# headstage-with-omnetics.net
KiCad netlist of a schematic drawn in EAGLE
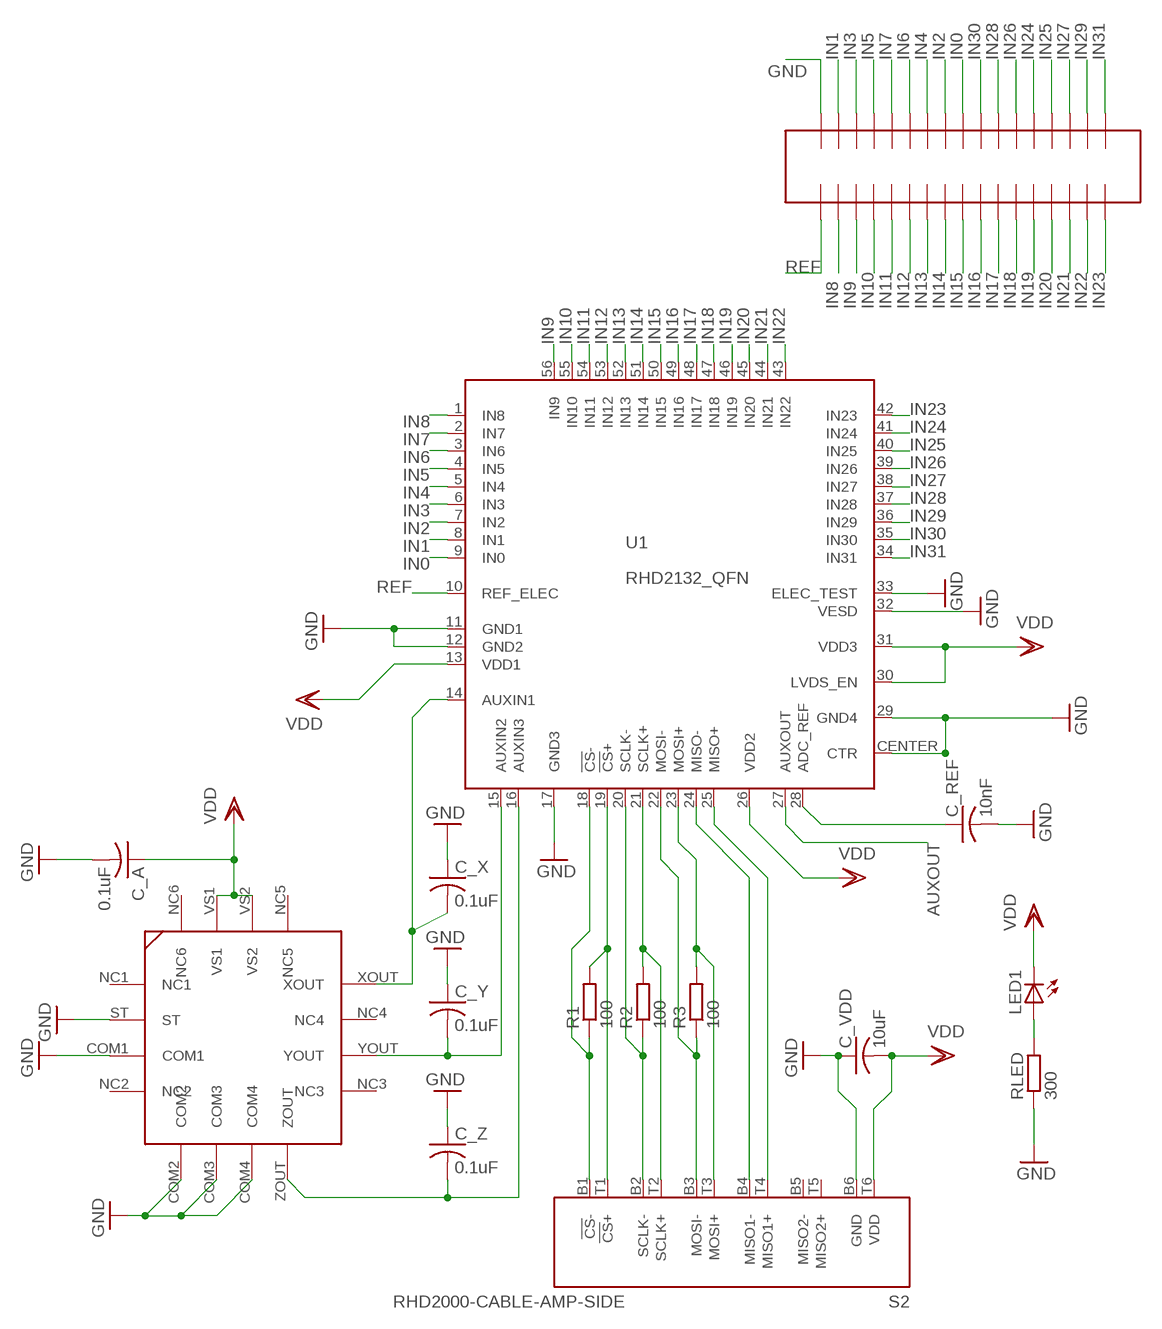
[diagram p0: schematic, sheet 1]

(export (version "E")
  (design (tool "Eeschema 10.0.6"))
  (components
    (comp (ref "C_A")
      (value "0.1uF")
      (footprint "eagle-import:C0402K")
      (libsource (lib "eagle-import") (part "resistor_C-USC0402K"))
    )
    (comp (ref "C_REF")
      (value "10nF")
      (footprint "eagle-import:C0402K")
      (libsource (lib "eagle-import") (part "resistor_C-USC0402K"))
    )
    (comp (ref "C_VDD")
      (value "10uF")
      (footprint "eagle-import:C0805")
      (libsource (lib "eagle-import") (part "C-USC0805"))
    )
    (comp (ref "C_X")
      (value "0.1uF")
      (footprint "eagle-import:C0402K")
      (libsource (lib "eagle-import") (part "resistor_C-USC0402K"))
    )
    (comp (ref "C_Y")
      (value "0.1uF")
      (footprint "eagle-import:C0402K")
      (libsource (lib "eagle-import") (part "resistor_C-USC0402K"))
    )
    (comp (ref "C_Z")
      (value "0.1uF")
      (footprint "eagle-import:C0402K")
      (libsource (lib "eagle-import") (part "resistor_C-USC0402K"))
    )
    (comp (ref "LED1")
      (value "LEDCHIPLED_0805")
      (footprint "eagle-import:CHIPLED_0805")
      (libsource (lib "eagle-import") (part "LEDCHIPLED_0805"))
    )
    (comp (ref "R1")
      (value "100")
      (footprint "eagle-import:R0402")
      (libsource (lib "eagle-import") (part "R-EU_R0402"))
    )
    (comp (ref "R2")
      (value "100")
      (footprint "eagle-import:R0402")
      (libsource (lib "eagle-import") (part "R-EU_R0402"))
    )
    (comp (ref "R3")
      (value "100")
      (footprint "eagle-import:R0402")
      (libsource (lib "eagle-import") (part "R-EU_R0402"))
    )
    (comp (ref "RLED")
      (value "300")
      (footprint "eagle-import:R0402")
      (libsource (lib "eagle-import") (part "R-EU_R0402"))
    )
    (comp (ref "S2")
      (value "RHD2000-CABLE-AMP-SIDE")
      (footprint "eagle-import:OMNETICS_PZN-12-AA")
      (libsource (lib "eagle-import") (part "RHD2000-CABLE-AMP-SIDE"))
    )
    (comp (ref "U$1")
      (value "ADXL335")
      (footprint "eagle-import:ADXL335")
      (libsource (lib "eagle-import") (part "ADXL335"))
    )
    (comp (ref "U$2")
      (value "FTSH-117BOARD-END")
      (footprint "eagle-import:FTSH-117-END")
      (libsource (lib "eagle-import") (part "FTSH-117BOARD-END"))
    )
    (comp (ref "U1")
      (value "RHD2132_QFN")
      (footprint "eagle-import:QFN56_8_X_8_LARGE")
      (libsource (lib "eagle-import") (part "RHD2132_QFN"))
    )
  )
  (nets
    (net (code "1") (name "/AUXOUT") (class "Default")
      (node (ref "U1") (pin "27") (pinfunction "AUXOUT_27") (pintype "tri_state"))
    )
    (net (code "2") (name "/IN0") (class "Default")
      (node (ref "U$2") (pin "P$26") (pinfunction "P$26_P$26") (pintype "bidirectional"))
      (node (ref "U1") (pin "9") (pinfunction "IN0_9") (pintype "input"))
    )
    (net (code "3") (name "/IN1") (class "Default")
      (node (ref "U$2") (pin "P$33") (pinfunction "P$33_P$33") (pintype "bidirectional"))
      (node (ref "U1") (pin "8") (pinfunction "IN1_8") (pintype "input"))
    )
    (net (code "4") (name "/IN2") (class "Default")
      (node (ref "U$2") (pin "P$27") (pinfunction "P$27_P$27") (pintype "bidirectional"))
      (node (ref "U1") (pin "7") (pinfunction "IN2_7") (pintype "input"))
    )
    (net (code "5") (name "/IN3") (class "Default")
      (node (ref "U$2") (pin "P$32") (pinfunction "P$32_P$32") (pintype "bidirectional"))
      (node (ref "U1") (pin "6") (pinfunction "IN3_6") (pintype "input"))
    )
    (net (code "6") (name "/IN4") (class "Default")
      (node (ref "U$2") (pin "P$28") (pinfunction "P$28_P$28") (pintype "bidirectional"))
      (node (ref "U1") (pin "5") (pinfunction "IN4_5") (pintype "input"))
    )
    (net (code "7") (name "/IN5") (class "Default")
      (node (ref "U$2") (pin "P$31") (pinfunction "P$31_P$31") (pintype "bidirectional"))
      (node (ref "U1") (pin "4") (pinfunction "IN5_4") (pintype "input"))
    )
    (net (code "8") (name "/IN6") (class "Default")
      (node (ref "U$2") (pin "P$29") (pinfunction "P$29_P$29") (pintype "bidirectional"))
      (node (ref "U1") (pin "3") (pinfunction "IN6_3") (pintype "input"))
    )
    (net (code "9") (name "/IN7") (class "Default")
      (node (ref "U$2") (pin "P$30") (pinfunction "P$30_P$30") (pintype "bidirectional"))
      (node (ref "U1") (pin "2") (pinfunction "IN7_2") (pintype "input"))
    )
    (net (code "10") (name "/IN8") (class "Default")
      (node (ref "U$2") (pin "P$2") (pinfunction "P$2_P$2") (pintype "bidirectional"))
      (node (ref "U1") (pin "1") (pinfunction "IN8_1") (pintype "input"))
    )
    (net (code "11") (name "/IN9") (class "Default")
      (node (ref "U$2") (pin "P$3") (pinfunction "P$3_P$3") (pintype "bidirectional"))
      (node (ref "U1") (pin "56") (pinfunction "IN9_56") (pintype "input"))
    )
    (net (code "12") (name "/IN10") (class "Default")
      (node (ref "U$2") (pin "P$4") (pinfunction "P$4_P$4") (pintype "bidirectional"))
      (node (ref "U1") (pin "55") (pinfunction "IN10_55") (pintype "input"))
    )
    (net (code "13") (name "/IN11") (class "Default")
      (node (ref "U$2") (pin "P$5") (pinfunction "P$5_P$5") (pintype "bidirectional"))
      (node (ref "U1") (pin "54") (pinfunction "IN11_54") (pintype "input"))
    )
    (net (code "14") (name "/IN12") (class "Default")
      (node (ref "U$2") (pin "P$6") (pinfunction "P$6_P$6") (pintype "bidirectional"))
      (node (ref "U1") (pin "53") (pinfunction "IN12_53") (pintype "input"))
    )
    (net (code "15") (name "/IN13") (class "Default")
      (node (ref "U$2") (pin "P$7") (pinfunction "P$7_P$7") (pintype "bidirectional"))
      (node (ref "U1") (pin "52") (pinfunction "IN13_52") (pintype "input"))
    )
    (net (code "16") (name "/IN14") (class "Default")
      (node (ref "U$2") (pin "P$8") (pinfunction "P$8_P$8") (pintype "bidirectional"))
      (node (ref "U1") (pin "51") (pinfunction "IN14_51") (pintype "input"))
    )
    (net (code "17") (name "/IN15") (class "Default")
      (node (ref "U$2") (pin "P$9") (pinfunction "P$9_P$9") (pintype "bidirectional"))
      (node (ref "U1") (pin "50") (pinfunction "IN15_50") (pintype "input"))
    )
    (net (code "18") (name "/IN16") (class "Default")
      (node (ref "U$2") (pin "P$10") (pinfunction "P$10_P$10") (pintype "bidirectional"))
      (node (ref "U1") (pin "49") (pinfunction "IN16_49") (pintype "input"))
    )
    (net (code "19") (name "/IN17") (class "Default")
      (node (ref "U$2") (pin "P$11") (pinfunction "P$11_P$11") (pintype "bidirectional"))
      (node (ref "U1") (pin "48") (pinfunction "IN17_48") (pintype "input"))
    )
    (net (code "20") (name "/IN18") (class "Default")
      (node (ref "U$2") (pin "P$12") (pinfunction "P$12_P$12") (pintype "bidirectional"))
      (node (ref "U1") (pin "47") (pinfunction "IN18_47") (pintype "input"))
    )
    (net (code "21") (name "/IN19") (class "Default")
      (node (ref "U$2") (pin "P$13") (pinfunction "P$13_P$13") (pintype "bidirectional"))
      (node (ref "U1") (pin "46") (pinfunction "IN19_46") (pintype "input"))
    )
    (net (code "22") (name "/IN20") (class "Default")
      (node (ref "U$2") (pin "P$14") (pinfunction "P$14_P$14") (pintype "bidirectional"))
      (node (ref "U1") (pin "45") (pinfunction "IN20_45") (pintype "input"))
    )
    (net (code "23") (name "/IN21") (class "Default")
      (node (ref "U$2") (pin "P$15") (pinfunction "P$15_P$15") (pintype "bidirectional"))
      (node (ref "U1") (pin "44") (pinfunction "IN21_44") (pintype "input"))
    )
    (net (code "24") (name "/IN22") (class "Default")
      (node (ref "U$2") (pin "P$16") (pinfunction "P$16_P$16") (pintype "bidirectional"))
      (node (ref "U1") (pin "43") (pinfunction "IN22_43") (pintype "input"))
    )
    (net (code "25") (name "/IN23") (class "Default")
      (node (ref "U$2") (pin "P$17") (pinfunction "P$17_P$17") (pintype "bidirectional"))
      (node (ref "U1") (pin "42") (pinfunction "IN23_42") (pintype "input"))
    )
    (net (code "26") (name "/IN24") (class "Default")
      (node (ref "U$2") (pin "P$22") (pinfunction "P$22_P$22") (pintype "bidirectional"))
      (node (ref "U1") (pin "41") (pinfunction "IN24_41") (pintype "input"))
    )
    (net (code "27") (name "/IN25") (class "Default")
      (node (ref "U$2") (pin "P$21") (pinfunction "P$21_P$21") (pintype "bidirectional"))
      (node (ref "U1") (pin "40") (pinfunction "IN25_40") (pintype "input"))
    )
    (net (code "28") (name "/IN26") (class "Default")
      (node (ref "U$2") (pin "P$23") (pinfunction "P$23_P$23") (pintype "bidirectional"))
      (node (ref "U1") (pin "39") (pinfunction "IN26_39") (pintype "input"))
    )
    (net (code "29") (name "/IN27") (class "Default")
      (node (ref "U$2") (pin "P$20") (pinfunction "P$20_P$20") (pintype "bidirectional"))
      (node (ref "U1") (pin "38") (pinfunction "IN27_38") (pintype "input"))
    )
    (net (code "30") (name "/IN28") (class "Default")
      (node (ref "U$2") (pin "P$24") (pinfunction "P$24_P$24") (pintype "bidirectional"))
      (node (ref "U1") (pin "37") (pinfunction "IN28_37") (pintype "input"))
    )
    (net (code "31") (name "/IN29") (class "Default")
      (node (ref "U$2") (pin "P$19") (pinfunction "P$19_P$19") (pintype "bidirectional"))
      (node (ref "U1") (pin "36") (pinfunction "IN29_36") (pintype "input"))
    )
    (net (code "32") (name "/IN30") (class "Default")
      (node (ref "U$2") (pin "P$25") (pinfunction "P$25_P$25") (pintype "bidirectional"))
      (node (ref "U1") (pin "35") (pinfunction "IN30_35") (pintype "input"))
    )
    (net (code "33") (name "/IN31") (class "Default")
      (node (ref "U$2") (pin "P$18") (pinfunction "P$18_P$18") (pintype "bidirectional"))
      (node (ref "U1") (pin "34") (pinfunction "IN31_34") (pintype "input"))
    )
    (net (code "34") (name "/REF") (class "Default")
      (node (ref "U$2") (pin "P$1") (pinfunction "P$1_P$1") (pintype "bidirectional"))
      (node (ref "U1") (pin "10") (pinfunction "REF_ELEC_10") (pintype "input"))
    )
    (net (code "35") (name "GND") (class "Default")
      (node (ref "C_A") (pin "2") (pinfunction "2_2") (pintype "passive"))
      (node (ref "C_REF") (pin "2") (pinfunction "2_2") (pintype "passive"))
      (node (ref "C_VDD") (pin "1") (pinfunction "1_1") (pintype "passive"))
      (node (ref "C_X") (pin "1") (pinfunction "1_1") (pintype "passive"))
      (node (ref "C_Y") (pin "1") (pinfunction "1_1") (pintype "passive"))
      (node (ref "C_Z") (pin "1") (pinfunction "1_1") (pintype "passive"))
      (node (ref "RLED") (pin "1") (pinfunction "1_1") (pintype "passive"))
      (node (ref "S2") (pin "B6") (pinfunction "GND_B6") (pintype "power_in"))
      (node (ref "U$1") (pin "COM1") (pinfunction "COM1_COM1") (pintype "bidirectional"))
      (node (ref "U$1") (pin "COM2") (pinfunction "COM2_COM2") (pintype "bidirectional"))
      (node (ref "U$1") (pin "COM3") (pinfunction "COM3_COM3") (pintype "bidirectional"))
      (node (ref "U$1") (pin "COM4") (pinfunction "COM4_COM4") (pintype "bidirectional"))
      (node (ref "U$1") (pin "ST") (pinfunction "ST_ST") (pintype "bidirectional"))
      (node (ref "U$2") (pin "P$34") (pinfunction "P$34_P$34") (pintype "bidirectional"))
      (node (ref "U1") (pin "11") (pinfunction "GND1_11") (pintype "power_in"))
      (node (ref "U1") (pin "12") (pinfunction "GND2_12") (pintype "power_in"))
      (node (ref "U1") (pin "17") (pinfunction "GND3_17") (pintype "power_in"))
      (node (ref "U1") (pin "29") (pinfunction "GND4_29") (pintype "power_in"))
      (node (ref "U1") (pin "32") (pinfunction "VESD_32") (pintype "power_in"))
      (node (ref "U1") (pin "33") (pinfunction "ELEC_TEST_33") (pintype "input"))
      (node (ref "U1") (pin "CENTER") (pinfunction "CTR_CENTER") (pintype "power_in"))
    )
    (net (code "36") (name "Net-(LED1-PadA)") (class "Default")
      (node (ref "LED1") (pin "A") (pinfunction "A_A") (pintype "passive"))
      (node (ref "RLED") (pin "2") (pinfunction "2_2") (pintype "passive"))
    )
    (net (code "37") (name "Net-(S2-MISO1+)") (class "Default")
      (node (ref "S2") (pin "T4") (pinfunction "MISO1+_T4") (pintype "bidirectional"))
      (node (ref "U1") (pin "25") (pinfunction "MISO+_25") (pintype "output"))
    )
    (net (code "38") (name "Net-(S2-MISO1-)") (class "Default")
      (node (ref "S2") (pin "B4") (pinfunction "MISO1-_B4") (pintype "bidirectional"))
      (node (ref "U1") (pin "24") (pinfunction "MISO-_24") (pintype "output"))
    )
    (net (code "39") (name "Net-(S2-MOSI+)") (class "Default")
      (node (ref "R3") (pin "2") (pinfunction "2_2") (pintype "passive"))
      (node (ref "S2") (pin "T3") (pinfunction "MOSI+_T3") (pintype "bidirectional"))
      (node (ref "U1") (pin "23") (pinfunction "MOSI+_23") (pintype "input"))
    )
    (net (code "40") (name "Net-(S2-MOSI-)") (class "Default")
      (node (ref "R3") (pin "1") (pinfunction "1_1") (pintype "passive"))
      (node (ref "S2") (pin "B3") (pinfunction "MOSI-_B3") (pintype "bidirectional"))
      (node (ref "U1") (pin "22") (pinfunction "MOSI-_22") (pintype "input"))
    )
    (net (code "41") (name "Net-(S2-SCLK+)") (class "Default")
      (node (ref "R2") (pin "2") (pinfunction "2_2") (pintype "passive"))
      (node (ref "S2") (pin "T2") (pinfunction "SCLK+_T2") (pintype "bidirectional"))
      (node (ref "U1") (pin "21") (pinfunction "SCLK+_21") (pintype "input"))
    )
    (net (code "42") (name "Net-(S2-SCLK-)") (class "Default")
      (node (ref "R2") (pin "1") (pinfunction "1_1") (pintype "passive"))
      (node (ref "S2") (pin "B2") (pinfunction "SCLK-_B2") (pintype "bidirectional"))
      (node (ref "U1") (pin "20") (pinfunction "SCLK-_20") (pintype "input"))
    )
    (net (code "43") (name "Net-(S2-~{CS}+)") (class "Default")
      (node (ref "R1") (pin "2") (pinfunction "2_2") (pintype "passive"))
      (node (ref "S2") (pin "T1") (pinfunction "~{CS}+_T1") (pintype "bidirectional"))
      (node (ref "U1") (pin "19") (pinfunction "~{CS}+_19") (pintype "input"))
    )
    (net (code "44") (name "Net-(S2-~{CS}-)") (class "Default")
      (node (ref "R1") (pin "1") (pinfunction "1_1") (pintype "passive"))
      (node (ref "S2") (pin "B1") (pinfunction "~{CS}-_B1") (pintype "bidirectional"))
      (node (ref "U1") (pin "18") (pinfunction "~{CS}-_18") (pintype "input"))
    )
    (net (code "45") (name "Net-(U1-ADC_REF)") (class "Default")
      (node (ref "C_REF") (pin "1") (pinfunction "1_1") (pintype "passive"))
      (node (ref "U1") (pin "28") (pinfunction "ADC_REF_28") (pintype "passive"))
    )
    (net (code "46") (name "Net-(U1-AUXIN1)") (class "Default")
      (node (ref "C_X") (pin "2") (pinfunction "2_2") (pintype "passive"))
      (node (ref "U$1") (pin "XOUT") (pinfunction "XOUT_XOUT") (pintype "bidirectional"))
      (node (ref "U1") (pin "14") (pinfunction "AUXIN1_14") (pintype "input"))
    )
    (net (code "47") (name "Net-(U1-AUXIN2)") (class "Default")
      (node (ref "C_Y") (pin "2") (pinfunction "2_2") (pintype "passive"))
      (node (ref "U$1") (pin "YOUT") (pinfunction "YOUT_YOUT") (pintype "bidirectional"))
      (node (ref "U1") (pin "15") (pinfunction "AUXIN2_15") (pintype "input"))
    )
    (net (code "48") (name "Net-(U1-AUXIN3)") (class "Default")
      (node (ref "C_Z") (pin "2") (pinfunction "2_2") (pintype "passive"))
      (node (ref "U$1") (pin "ZOUT") (pinfunction "ZOUT_ZOUT") (pintype "bidirectional"))
      (node (ref "U1") (pin "16") (pinfunction "AUXIN3_16") (pintype "input"))
    )
    (net (code "49") (name "VDD") (class "Default")
      (node (ref "C_A") (pin "1") (pinfunction "1_1") (pintype "passive"))
      (node (ref "C_VDD") (pin "2") (pinfunction "2_2") (pintype "passive"))
      (node (ref "LED1") (pin "C") (pinfunction "C_C") (pintype "passive"))
      (node (ref "S2") (pin "T6") (pinfunction "VDD_T6") (pintype "bidirectional"))
      (node (ref "U$1") (pin "VS1") (pinfunction "VS1_VS1") (pintype "bidirectional"))
      (node (ref "U$1") (pin "VS2") (pinfunction "VS2_VS2") (pintype "bidirectional"))
      (node (ref "U1") (pin "13") (pinfunction "VDD1_13") (pintype "power_in"))
      (node (ref "U1") (pin "26") (pinfunction "VDD2_26") (pintype "power_in"))
      (node (ref "U1") (pin "30") (pinfunction "LVDS_EN_30") (pintype "input"))
      (node (ref "U1") (pin "31") (pinfunction "VDD3_31") (pintype "power_in"))
    )
    (net (code "50") (name "unconnected-(S2-MISO2+-PadT5)") (class "Default")
      (node (ref "S2") (pin "T5") (pinfunction "MISO2+_T5") (pintype "bidirectional"))
    )
    (net (code "51") (name "unconnected-(S2-MISO2--PadB5)") (class "Default")
      (node (ref "S2") (pin "B5") (pinfunction "MISO2-_B5") (pintype "bidirectional"))
    )
    (net (code "52") (name "unconnected-(U$1-PadNC1)") (class "Default")
      (node (ref "U$1") (pin "NC1") (pinfunction "NC1_NC1") (pintype "bidirectional"))
    )
    (net (code "53") (name "unconnected-(U$1-PadNC2)") (class "Default")
      (node (ref "U$1") (pin "NC2") (pinfunction "NC2_NC2") (pintype "bidirectional"))
    )
    (net (code "54") (name "unconnected-(U$1-PadNC3)") (class "Default")
      (node (ref "U$1") (pin "NC3") (pinfunction "NC3_NC3") (pintype "bidirectional"))
    )
    (net (code "55") (name "unconnected-(U$1-PadNC4)") (class "Default")
      (node (ref "U$1") (pin "NC4") (pinfunction "NC4_NC4") (pintype "bidirectional"))
    )
    (net (code "56") (name "unconnected-(U$1-PadNC5)") (class "Default")
      (node (ref "U$1") (pin "NC5") (pinfunction "NC5_NC5") (pintype "bidirectional"))
    )
    (net (code "57") (name "unconnected-(U$1-PadNC6)") (class "Default")
      (node (ref "U$1") (pin "NC6") (pinfunction "NC6_NC6") (pintype "bidirectional"))
    )
  )
)
